# EPDSchedule.net
KiCad netlist of a schematic drawn in EasyEDA Pro
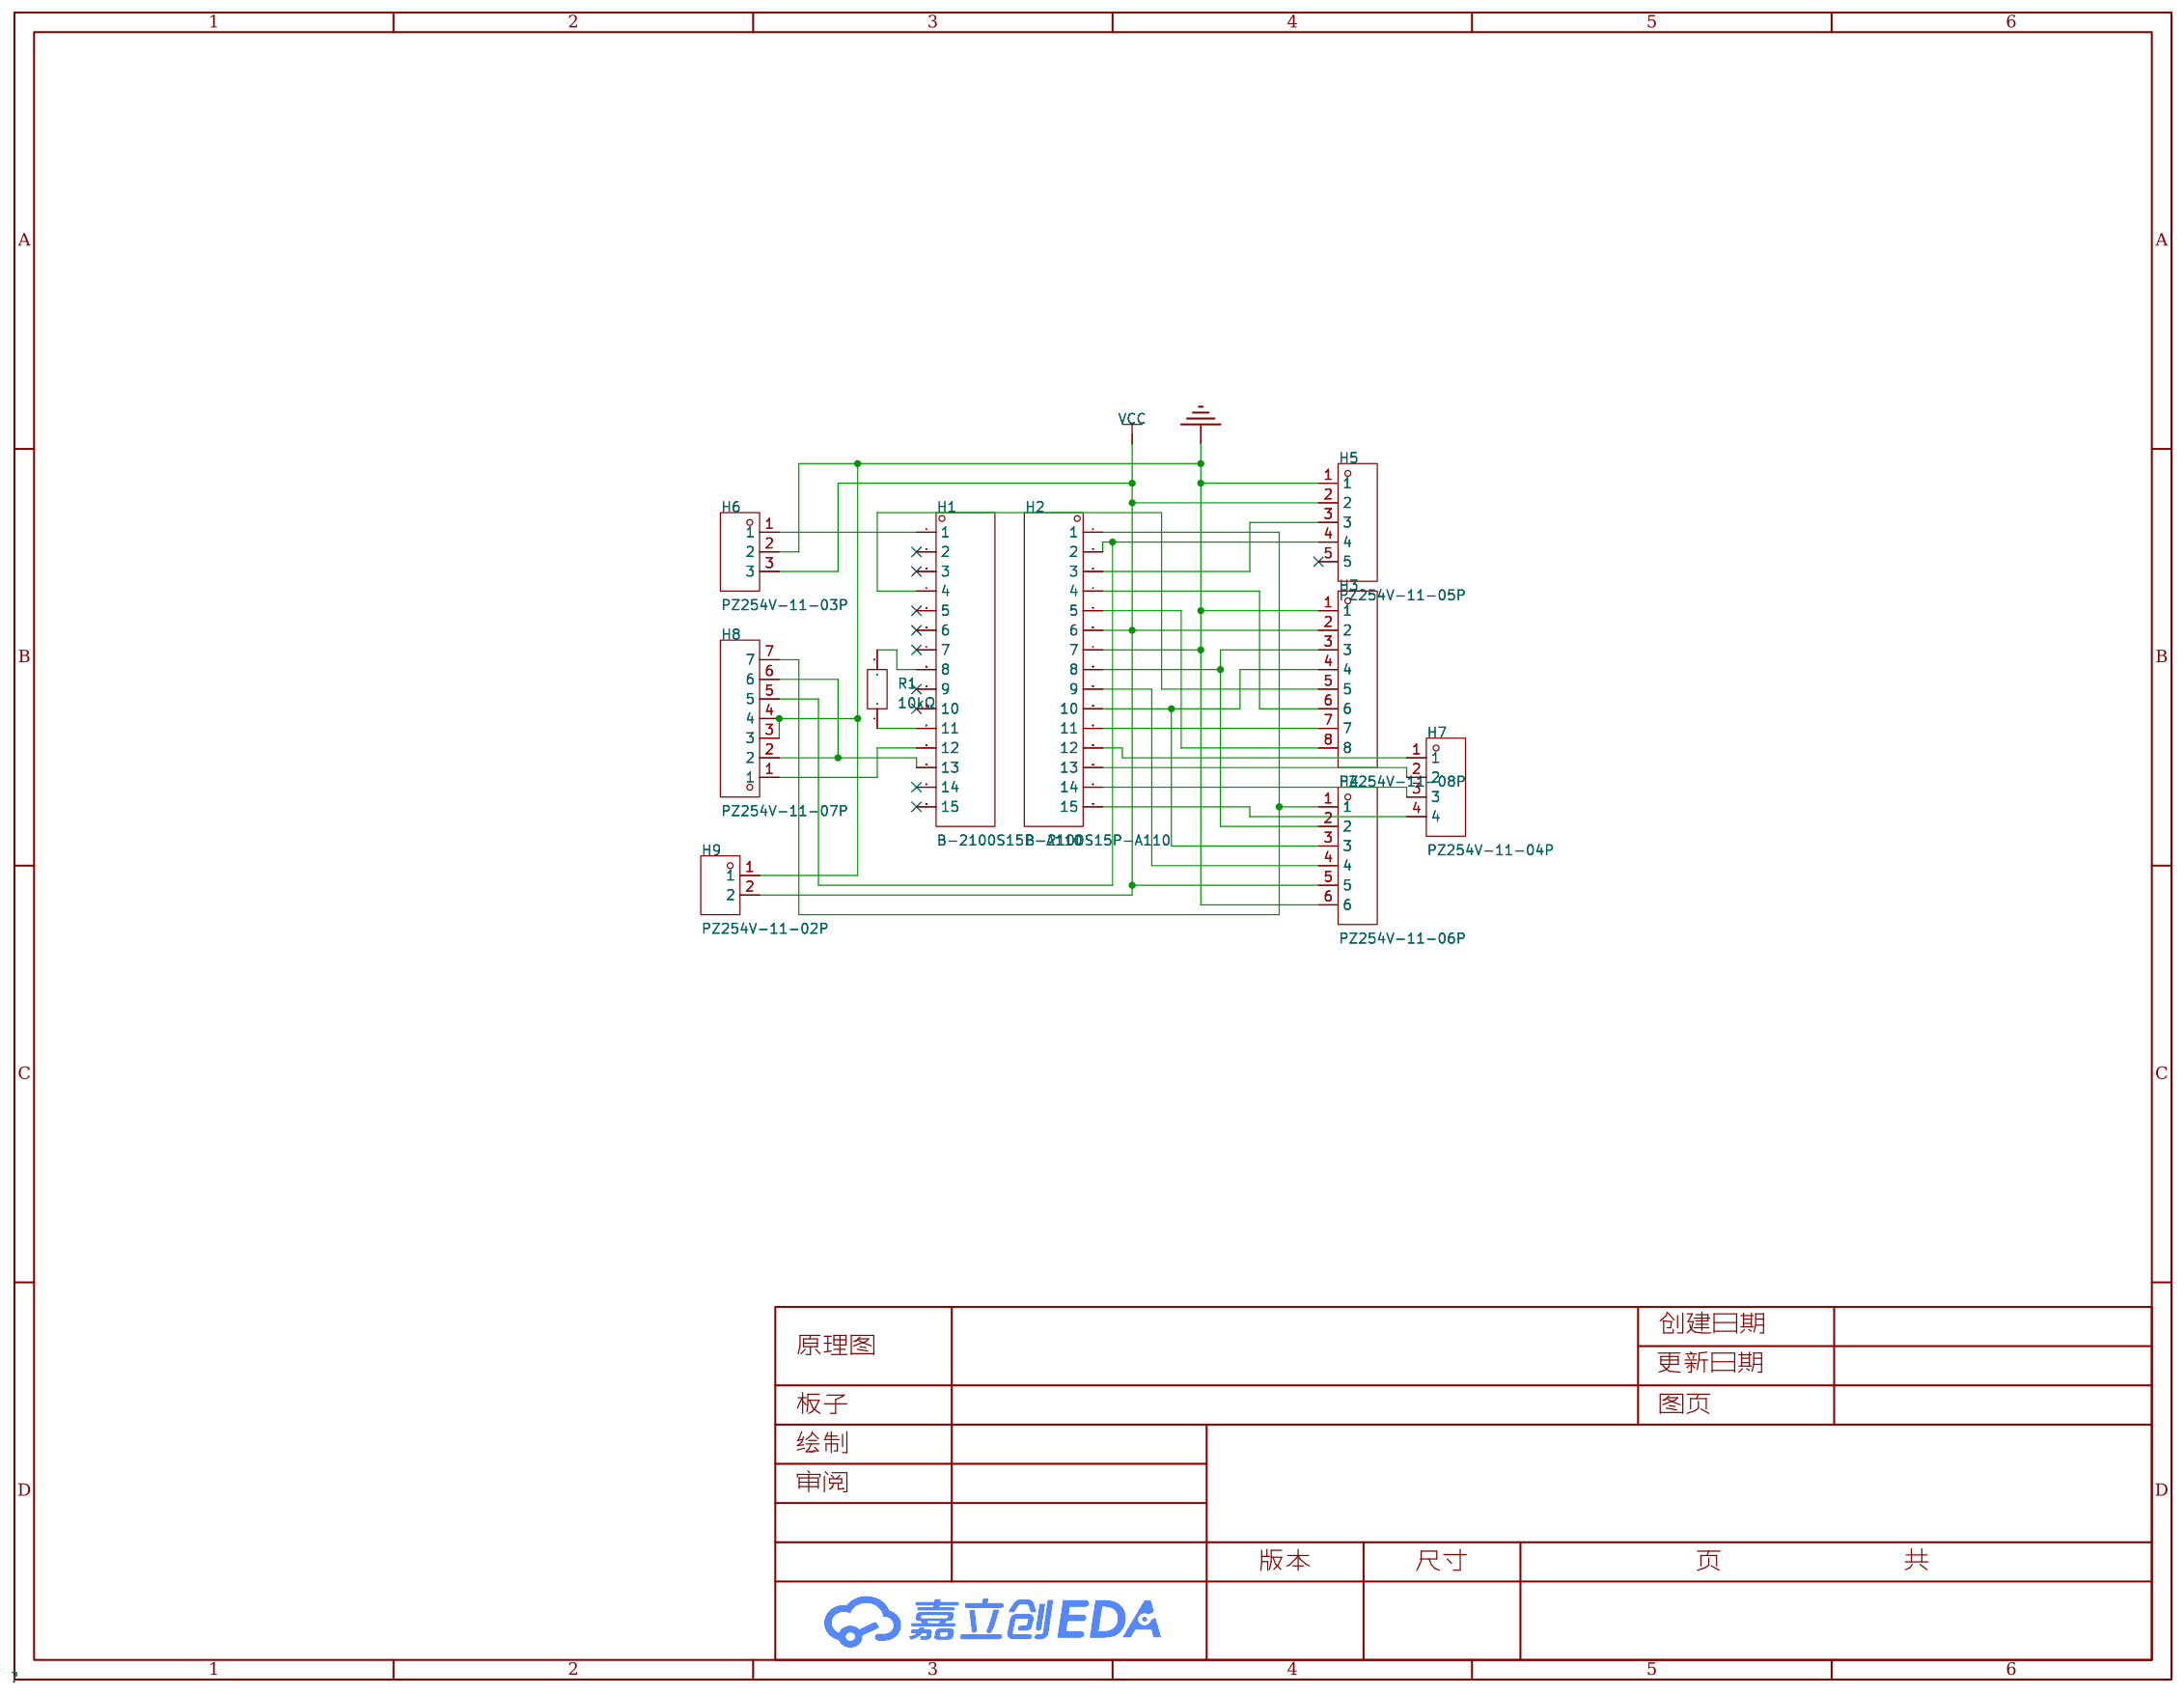
[diagram p0: schematic sheet]

(export (version "E")
  (design (tool "Eeschema 10.0.6"))
  (components
    (comp (ref "H1")
      (value "B-2100S15P-A110")
      (footprint "easyedapro:HDR-TH_15P-P2.54-V-M")
      (fields (field (name "Manufacturer") "Ckmtw(灿科盟)"))
      (libsource (lib "easyedapro") (part "Header-Male-2.54_1x15"))
    )
    (comp (ref "H2")
      (value "B-2100S15P-A110")
      (footprint "easyedapro:HDR-TH_15P-P2.54-V-M")
      (fields (field (name "Manufacturer") "Ckmtw(灿科盟)"))
      (libsource (lib "easyedapro") (part "Header-Male-2.54_1x15"))
    )
    (comp (ref "H3")
      (value "PZ254V-11-08P")
      (footprint "easyedapro:HDR-TH_8P-P2.54-V-M")
      (fields (field (name "Manufacturer") "XFCN(兴飞)"))
      (libsource (lib "easyedapro") (part "PZ254V-11-08P"))
    )
    (comp (ref "H4")
      (value "PZ254V-11-06P")
      (footprint "easyedapro:HDR-TH_6P-P2.54-V-M")
      (fields (field (name "Manufacturer") "XFCN(兴飞)"))
      (libsource (lib "easyedapro") (part "PZ254V-11-06P"))
    )
    (comp (ref "H5")
      (value "PZ254V-11-05P")
      (footprint "easyedapro:HDR-TH_5P-P2.54-V-M")
      (fields (field (name "Manufacturer") "XFCN(兴飞)"))
      (libsource (lib "easyedapro") (part "PZ254V-11-05P"))
    )
    (comp (ref "H6")
      (value "PZ254V-11-03P")
      (footprint "easyedapro:HDR-TH_3P-P2.54-V-M")
      (fields (field (name "Manufacturer") "XFCN(兴飞)"))
      (libsource (lib "easyedapro") (part "PZ254V-11-03P"))
    )
    (comp (ref "H7")
      (value "PZ254V-11-04P")
      (footprint "easyedapro:HDR-TH_4P-P2.54-V-M")
      (fields (field (name "Manufacturer") "XFCN(兴飞)"))
      (libsource (lib "easyedapro") (part "PZ254V-11-04P_C2691448"))
    )
    (comp (ref "H8")
      (value "PZ254V-11-07P")
      (footprint "easyedapro:HDR-TH_7P-P2.54-V-M")
      (fields (field (name "Manufacturer") "XFCN(兴飞)"))
      (libsource (lib "easyedapro") (part "PZ254V-11-07P"))
    )
    (comp (ref "H9")
      (value "PZ254V-11-02P")
      (footprint "easyedapro:HDR-TH_2P-P2.54-V-M")
      (fields (field (name "Manufacturer") "XFCN(兴飞)"))
      (libsource (lib "easyedapro") (part "PZ254V-11-02P"))
    )
    (comp (ref "R1")
      (value "10kΩ")
      (footprint "easyedapro:RES-TH_BD2.4-L6.3-P10.30-D0.6")
      (description "电阻类型:金属膜电阻;阻值:10kΩ;精度:±1%;功率:250mW;温度系数:±50ppm/°C;")
      (fields
        (field (name "Manufacturer Part") "RN1/4W10KFT/BA1")
        (field (name "Manufacturer") "Tyohm(幸亚电阻)")
      )
      (libsource (lib "easyedapro") (part "RN 1/4W 10K F T/B A1"))
    )
  )
  (nets
    (net (code "1") (name "GND") (class "Default")
      (node (ref "H2") (pin "7") (pinfunction "7_7") (pintype "input"))
      (node (ref "H3") (pin "1") (pinfunction "1_1") (pintype "input"))
      (node (ref "H4") (pin "6") (pinfunction "6_6") (pintype "unspecified"))
      (node (ref "H5") (pin "1") (pinfunction "1_1") (pintype "input"))
      (node (ref "H6") (pin "2") (pinfunction "2_2") (pintype "input"))
      (node (ref "H8") (pin "3") (pinfunction "3_3") (pintype "unspecified"))
      (node (ref "H8") (pin "4") (pinfunction "4_4") (pintype "unspecified"))
      (node (ref "H9") (pin "1") (pinfunction "1_1") (pintype "unspecified"))
    )
    (net (code "2") (name "Net-(H1-Pad1)") (class "Default")
      (node (ref "H1") (pin "1") (pinfunction "1_1") (pintype "input"))
      (node (ref "H6") (pin "1") (pinfunction "1_1") (pintype "input"))
    )
    (net (code "3") (name "Net-(H1-Pad4)") (class "Default")
      (node (ref "H1") (pin "4") (pinfunction "4_4") (pintype "input"))
      (node (ref "H3") (pin "5") (pinfunction "5_5") (pintype "input"))
    )
    (net (code "4") (name "Net-(H1-Pad8)") (class "Default")
      (node (ref "H1") (pin "8") (pinfunction "8_8") (pintype "input"))
      (node (ref "R1") (pin "2") (pinfunction "2_2") (pintype "unspecified"))
    )
    (net (code "5") (name "Net-(H1-Pad11)") (class "Default")
      (node (ref "H1") (pin "11") (pinfunction "11_11") (pintype "input"))
      (node (ref "R1") (pin "1") (pinfunction "1_1") (pintype "unspecified"))
    )
    (net (code "6") (name "Net-(H1-Pad12)") (class "Default")
      (node (ref "H1") (pin "12") (pinfunction "12_12") (pintype "input"))
      (node (ref "H8") (pin "1") (pinfunction "1_1") (pintype "unspecified"))
    )
    (net (code "7") (name "Net-(H1-Pad13)") (class "Default")
      (node (ref "H1") (pin "13") (pinfunction "13_13") (pintype "input"))
      (node (ref "H8") (pin "2") (pinfunction "2_2") (pintype "unspecified"))
      (node (ref "H8") (pin "6") (pinfunction "6_6") (pintype "unspecified"))
    )
    (net (code "8") (name "Net-(H2-Pad1)") (class "Default")
      (node (ref "H2") (pin "1") (pinfunction "1_1") (pintype "input"))
      (node (ref "H4") (pin "1") (pinfunction "1_1") (pintype "unspecified"))
      (node (ref "H8") (pin "7") (pinfunction "7_7") (pintype "unspecified"))
    )
    (net (code "9") (name "Net-(H2-Pad2)") (class "Default")
      (node (ref "H2") (pin "2") (pinfunction "2_2") (pintype "input"))
      (node (ref "H5") (pin "4") (pinfunction "4_4") (pintype "input"))
      (node (ref "H8") (pin "5") (pinfunction "5_5") (pintype "unspecified"))
    )
    (net (code "10") (name "Net-(H2-Pad3)") (class "Default")
      (node (ref "H2") (pin "3") (pinfunction "3_3") (pintype "input"))
      (node (ref "H5") (pin "3") (pinfunction "3_3") (pintype "input"))
    )
    (net (code "11") (name "Net-(H2-Pad4)") (class "Default")
      (node (ref "H2") (pin "4") (pinfunction "4_4") (pintype "input"))
      (node (ref "H3") (pin "6") (pinfunction "6_6") (pintype "input"))
    )
    (net (code "12") (name "Net-(H2-Pad5)") (class "Default")
      (node (ref "H2") (pin "5") (pinfunction "5_5") (pintype "input"))
      (node (ref "H3") (pin "8") (pinfunction "8_8") (pintype "input"))
    )
    (net (code "13") (name "Net-(H2-Pad8)") (class "Default")
      (node (ref "H2") (pin "8") (pinfunction "8_8") (pintype "input"))
      (node (ref "H3") (pin "3") (pinfunction "3_3") (pintype "input"))
      (node (ref "H4") (pin "2") (pinfunction "2_2") (pintype "unspecified"))
    )
    (net (code "14") (name "Net-(H2-Pad9)") (class "Default")
      (node (ref "H2") (pin "9") (pinfunction "9_9") (pintype "input"))
      (node (ref "H4") (pin "4") (pinfunction "4_4") (pintype "unspecified"))
    )
    (net (code "15") (name "Net-(H2-Pad10)") (class "Default")
      (node (ref "H2") (pin "10") (pinfunction "10_10") (pintype "input"))
      (node (ref "H3") (pin "4") (pinfunction "4_4") (pintype "input"))
      (node (ref "H4") (pin "3") (pinfunction "3_3") (pintype "unspecified"))
    )
    (net (code "16") (name "Net-(H2-Pad11)") (class "Default")
      (node (ref "H2") (pin "11") (pinfunction "11_11") (pintype "input"))
      (node (ref "H3") (pin "7") (pinfunction "7_7") (pintype "input"))
    )
    (net (code "17") (name "Net-(H2-Pad12)") (class "Default")
      (node (ref "H2") (pin "12") (pinfunction "12_12") (pintype "input"))
      (node (ref "H7") (pin "1") (pinfunction "1_1") (pintype "unspecified"))
    )
    (net (code "18") (name "Net-(H2-Pad13)") (class "Default")
      (node (ref "H2") (pin "13") (pinfunction "13_13") (pintype "input"))
      (node (ref "H7") (pin "2") (pinfunction "2_2") (pintype "unspecified"))
    )
    (net (code "19") (name "Net-(H2-Pad14)") (class "Default")
      (node (ref "H2") (pin "14") (pinfunction "14_14") (pintype "input"))
      (node (ref "H7") (pin "3") (pinfunction "3_3") (pintype "unspecified"))
    )
    (net (code "20") (name "Net-(H2-Pad15)") (class "Default")
      (node (ref "H2") (pin "15") (pinfunction "15_15") (pintype "input"))
      (node (ref "H7") (pin "4") (pinfunction "4_4") (pintype "unspecified"))
    )
    (net (code "21") (name "VCC") (class "Default")
      (node (ref "H2") (pin "6") (pinfunction "6_6") (pintype "input"))
      (node (ref "H3") (pin "2") (pinfunction "2_2") (pintype "input"))
      (node (ref "H4") (pin "5") (pinfunction "5_5") (pintype "unspecified"))
      (node (ref "H5") (pin "2") (pinfunction "2_2") (pintype "input"))
      (node (ref "H6") (pin "3") (pinfunction "3_3") (pintype "input"))
      (node (ref "H9") (pin "2") (pinfunction "2_2") (pintype "unspecified"))
    )
    (net (code "22") (name "unconnected-(H1-Pad2)") (class "Default")
      (node (ref "H1") (pin "2") (pinfunction "2_2") (pintype "input+no_connect"))
    )
    (net (code "23") (name "unconnected-(H1-Pad3)") (class "Default")
      (node (ref "H1") (pin "3") (pinfunction "3_3") (pintype "input+no_connect"))
    )
    (net (code "24") (name "unconnected-(H1-Pad5)") (class "Default")
      (node (ref "H1") (pin "5") (pinfunction "5_5") (pintype "input+no_connect"))
    )
    (net (code "25") (name "unconnected-(H1-Pad6)") (class "Default")
      (node (ref "H1") (pin "6") (pinfunction "6_6") (pintype "input+no_connect"))
    )
    (net (code "26") (name "unconnected-(H1-Pad7)") (class "Default")
      (node (ref "H1") (pin "7") (pinfunction "7_7") (pintype "input+no_connect"))
    )
    (net (code "27") (name "unconnected-(H1-Pad9)") (class "Default")
      (node (ref "H1") (pin "9") (pinfunction "9_9") (pintype "input+no_connect"))
    )
    (net (code "28") (name "unconnected-(H1-Pad10)") (class "Default")
      (node (ref "H1") (pin "10") (pinfunction "10_10") (pintype "input+no_connect"))
    )
    (net (code "29") (name "unconnected-(H1-Pad14)") (class "Default")
      (node (ref "H1") (pin "14") (pinfunction "14_14") (pintype "input+no_connect"))
    )
    (net (code "30") (name "unconnected-(H1-Pad15)") (class "Default")
      (node (ref "H1") (pin "15") (pinfunction "15_15") (pintype "input+no_connect"))
    )
    (net (code "31") (name "unconnected-(H5-Pad5)") (class "Default")
      (node (ref "H5") (pin "5") (pinfunction "5_5") (pintype "input+no_connect"))
    )
  )
)
